# DONGLE02.net
KiCad netlist of a schematic drawn in Altium Designer
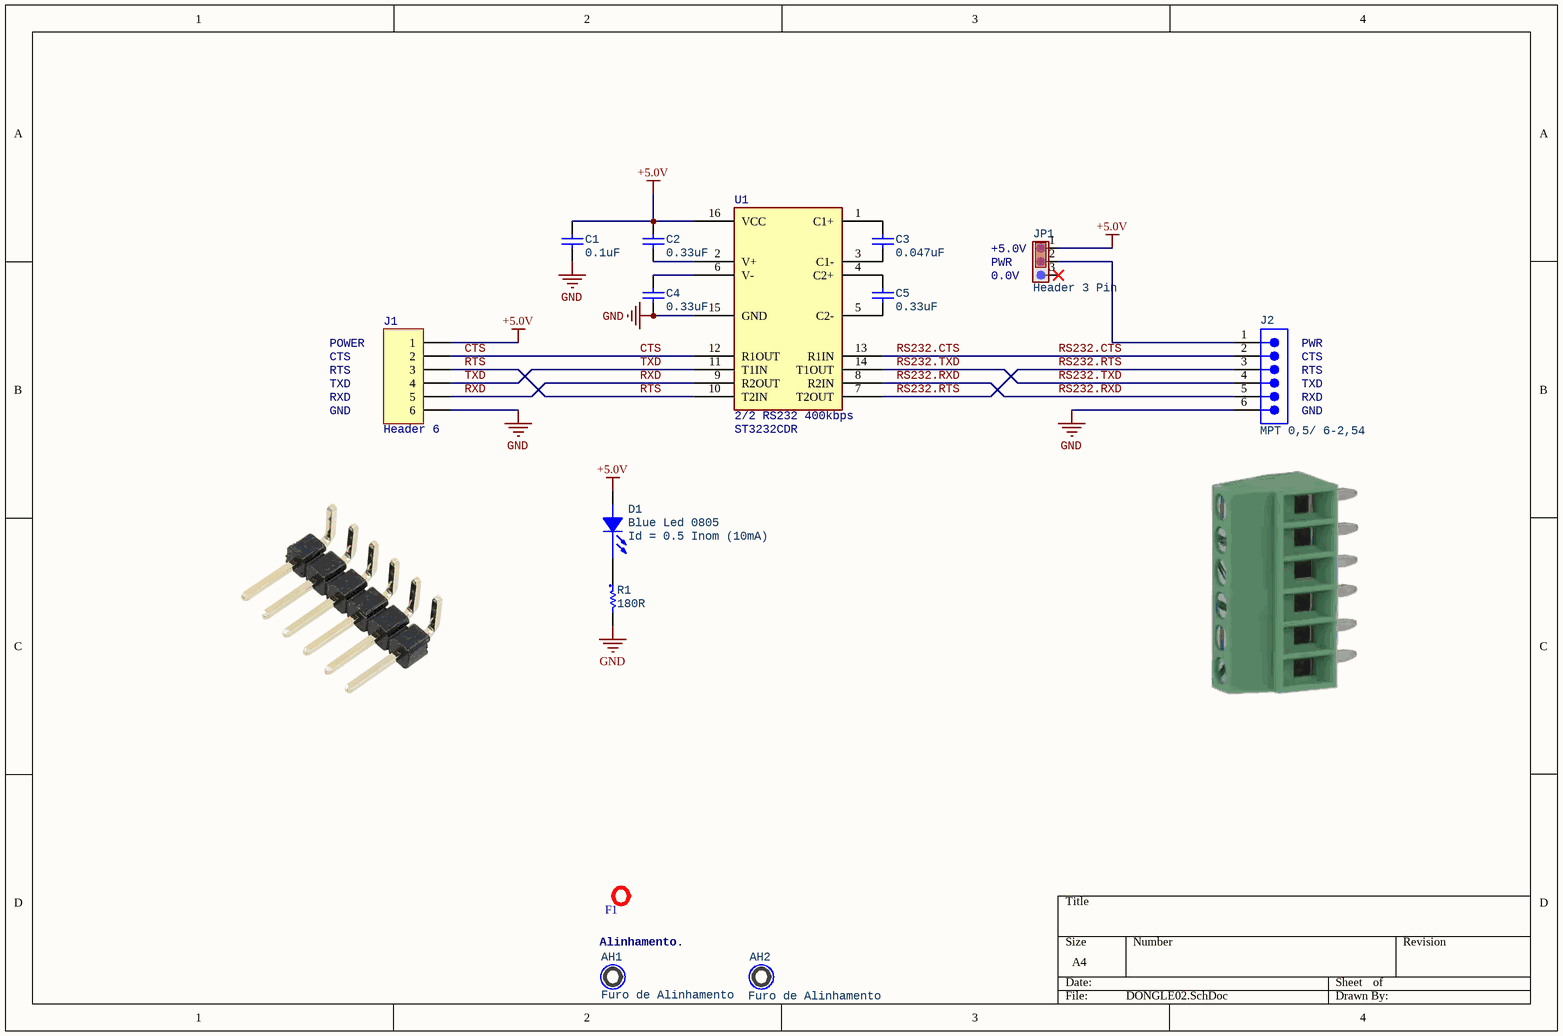
[diagram p0: DONGLE02.SchDoc]

(export (version "E")
  (design (tool "Eeschema 10.0.6"))
  (components
    (comp (ref "AH1")
      (value "Furo de Alinhamento")
      (footprint "AH_2.0MMD")
      (libsource (lib "My_Library") (part "Aligment Hole M2"))
    )
    (comp (ref "AH2")
      (value "Furo de Alinhamento")
      (footprint "AH_2.0MMD")
      (libsource (lib "My_Library") (part "Aligment Hole M2"))
    )
    (comp (ref "C1")
      (value "0.1uF")
      (footprint "C0805")
      (description "0.1 µF ±10% 100V Ceramic Capacitor X7R 0805 (2012 Metric)")
      (fields (field (name "MANUFACTURER") "Murata Electronics"))
      (libsource (lib "My_Library") (part "CAP"))
    )
    (comp (ref "C2")
      (value "0.33uF")
      (footprint "C0805")
      (description "0.33 µF ±5% 25V Ceramic Capacitor X7R 0805 (2012 Metric)")
      (fields (field (name "MANUFACTURER") "KEMET"))
      (libsource (lib "My_Library") (part "CAP"))
    )
    (comp (ref "C3")
      (value "0.047uF")
      (footprint "C0805")
      (description "0.047 µF ±5% 25V Ceramic Capacitor X7R 0805 (2012 Metric)")
      (fields (field (name "MANUFACTURER") "KYOCERA AVX"))
      (libsource (lib "My_Library") (part "CAP"))
    )
    (comp (ref "C4")
      (value "0.33uF")
      (footprint "C0805")
      (description "0.33 µF ±5% 25V Ceramic Capacitor X7R 0805 (2012 Metric)")
      (fields (field (name "MANUFACTURER") "KEMET"))
      (libsource (lib "My_Library") (part "CAP"))
    )
    (comp (ref "C5")
      (value "0.33uF")
      (footprint "C0805")
      (description "0.33 µF ±5% 25V Ceramic Capacitor X7R 0805 (2012 Metric)")
      (fields (field (name "MANUFACTURER") "KEMET"))
      (libsource (lib "My_Library") (part "CAP"))
    )
    (comp (ref "D1")
      (value "Blue Led 0805")
      (footprint "LED 0805")
      (description "Blue 470nm LED Indication - Discrete 3.2V 0805 (2012 Metric)")
      (fields (field (name "MANUFACTURER") "Würth Elektronik") (field (name "INFO") "Id = 0.5 Inom (10mA)"))
      (libsource (lib "My_Library") (part "LED GREEN 0805"))
    )
    (comp (ref "F1")
      (value "~")
      (footprint "FIDUCIAL")
      (description "FIDUCIAL MARK")
      (libsource (lib "My_Library") (part "FIDUCIAL"))
    )
    (comp (ref "J1")
      (value "Header 6")
      (footprint "BERG-M-6V-H-INV")
      (description "Connector Header Through Hole, Right Angle 6 position 0.100\" (2.54mm)")
      (fields (field (name "MANUFACTURER") "Adam Tech"))
      (libsource (lib "Miscellaneous Connectors") (part "Header 6"))
    )
    (comp (ref "J2")
      (value "MPT 0,5/ 6-2,54")
      (footprint "1725698")
      (description "6 Position Wire to Board Terminal Block Horizontal with Board 0.100\" (2.54mm) Through Hole")
      (fields (field (name "MANUFACTURER") "Phoenix Contact"))
      (libsource (lib "691101710002_Altium_WR-TBL_rev23c") (part "691322110006"))
    )
    (comp (ref "JP1")
      (value "Header 3 Pin")
      (footprint "JMP-3-PTH-180")
      (description "3 Pin Jumper")
      (fields (field (name "MANUFACTURER") "Würth Elektronik"))
      (libsource (lib "My_Library") (part "Jumper 3"))
    )
    (comp (ref "R1")
      (value "180R")
      (footprint "R0805")
      (description "180 Ohms ±1% 0.25W, 1/4W Chip Resistor 0805 (2012 Metric) Anti-Sulfur Thin Film")
      (fields (field (name "MANUFACTURER") "Stackpole Electronics Inc"))
      (libsource (lib "My_Library") (part "RESISTOR"))
    )
    (comp (ref "U1")
      (value "2/2 RS232 400kbps")
      (footprint "SOIC16N")
      (description "2/2 Transceiver Full RS232 16-SO")
      (fields
        (field (name "MANUFACTURER P/N") "ST3232CDR")
        (field (name "MANUFACTURER") "STMicroelectronics")
      )
      (libsource (lib "My_Library") (part "CI SMD ST3232CDR-SO16"))
    )
  )
  (nets
    (net (code "1") (name "+5.0V") (class "Default")
      (node (ref "C1") (pin "1") (pinfunction "1_1") (pintype "passive"))
      (node (ref "C2") (pin "1") (pinfunction "1_1") (pintype "passive"))
      (node (ref "D1") (pin "A") (pinfunction "A_A") (pintype "passive"))
      (node (ref "J1") (pin "1") (pinfunction "1_1") (pintype "passive"))
      (node (ref "JP1") (pin "1") (pinfunction "1_1") (pintype "passive"))
      (node (ref "U1") (pin "16") (pinfunction "VCC_16") (pintype "passive"))
    )
    (net (code "2") (name "/CTS") (class "Default")
      (node (ref "J1") (pin "2") (pinfunction "2_2") (pintype "passive"))
      (node (ref "U1") (pin "12") (pinfunction "R1OUT_12") (pintype "passive"))
    )
    (net (code "3") (name "/RS232.CTS") (class "Default")
      (node (ref "J2") (pin "2") (pinfunction "2_2") (pintype "passive"))
      (node (ref "U1") (pin "13") (pinfunction "R1IN_13") (pintype "passive"))
    )
    (net (code "4") (name "/RS232.RTS") (class "Default")
      (node (ref "J2") (pin "3") (pinfunction "3_3") (pintype "passive"))
      (node (ref "U1") (pin "7") (pinfunction "T2OUT_7") (pintype "passive"))
    )
    (net (code "5") (name "/RS232.RXD") (class "Default")
      (node (ref "J2") (pin "5") (pinfunction "5_5") (pintype "passive"))
      (node (ref "U1") (pin "8") (pinfunction "R2IN_8") (pintype "passive"))
    )
    (net (code "6") (name "/RS232.TXD") (class "Default")
      (node (ref "J2") (pin "4") (pinfunction "4_4") (pintype "passive"))
      (node (ref "U1") (pin "14") (pinfunction "T1OUT_14") (pintype "passive"))
    )
    (net (code "7") (name "/RTS") (class "Default")
      (node (ref "J1") (pin "3") (pinfunction "3_3") (pintype "passive"))
      (node (ref "U1") (pin "10") (pinfunction "T2IN_10") (pintype "passive"))
    )
    (net (code "8") (name "/RXD") (class "Default")
      (node (ref "J1") (pin "5") (pinfunction "5_5") (pintype "passive"))
      (node (ref "U1") (pin "9") (pinfunction "R2OUT_9") (pintype "passive"))
    )
    (net (code "9") (name "/TXD") (class "Default")
      (node (ref "J1") (pin "4") (pinfunction "4_4") (pintype "passive"))
      (node (ref "U1") (pin "11") (pinfunction "T1IN_11") (pintype "passive"))
    )
    (net (code "10") (name "GND") (class "Default")
      (node (ref "C1") (pin "2") (pinfunction "2_2") (pintype "passive"))
      (node (ref "C4") (pin "2") (pinfunction "2_2") (pintype "passive"))
      (node (ref "J1") (pin "6") (pinfunction "6_6") (pintype "passive"))
      (node (ref "J2") (pin "6") (pinfunction "6_6") (pintype "passive"))
      (node (ref "R1") (pin "2") (pinfunction "2_2") (pintype "passive"))
      (node (ref "U1") (pin "15") (pinfunction "GND_15") (pintype "passive"))
    )
    (net (code "11") (name "Net-(D1-PadK)") (class "Default")
      (node (ref "D1") (pin "K") (pinfunction "K_K") (pintype "passive"))
      (node (ref "R1") (pin "1") (pinfunction "1_1") (pintype "passive"))
    )
    (net (code "12") (name "Net-(J2-Pad1)") (class "Default")
      (node (ref "J2") (pin "1") (pinfunction "1_1") (pintype "passive"))
      (node (ref "JP1") (pin "2") (pinfunction "2_2") (pintype "passive"))
    )
    (net (code "13") (name "Net-(U1-C1+)") (class "Default")
      (node (ref "C3") (pin "1") (pinfunction "1_1") (pintype "passive"))
      (node (ref "U1") (pin "1") (pinfunction "C1+_1") (pintype "passive"))
    )
    (net (code "14") (name "Net-(U1-C1-)") (class "Default")
      (node (ref "C3") (pin "2") (pinfunction "2_2") (pintype "passive"))
      (node (ref "U1") (pin "3") (pinfunction "C1-_3") (pintype "passive"))
    )
    (net (code "15") (name "Net-(U1-C2+)") (class "Default")
      (node (ref "C5") (pin "1") (pinfunction "1_1") (pintype "passive"))
      (node (ref "U1") (pin "4") (pinfunction "C2+_4") (pintype "passive"))
    )
    (net (code "16") (name "Net-(U1-C2-)") (class "Default")
      (node (ref "C5") (pin "2") (pinfunction "2_2") (pintype "passive"))
      (node (ref "U1") (pin "5") (pinfunction "C2-_5") (pintype "passive"))
    )
    (net (code "17") (name "Net-(U1-V+)") (class "Default")
      (node (ref "C2") (pin "2") (pinfunction "2_2") (pintype "passive"))
      (node (ref "U1") (pin "2") (pinfunction "V+_2") (pintype "passive"))
    )
    (net (code "18") (name "Net-(U1-V-)") (class "Default")
      (node (ref "C4") (pin "1") (pinfunction "1_1") (pintype "passive"))
      (node (ref "U1") (pin "6") (pinfunction "V-_6") (pintype "passive"))
    )
    (net (code "19") (name "unconnected-(JP1-Pad3)") (class "Default")
      (node (ref "JP1") (pin "3") (pinfunction "3_3") (pintype "passive+no_connect"))
    )
  )
)
